# opencmpp.net
KiCad netlist of a schematic drawn in EAGLE
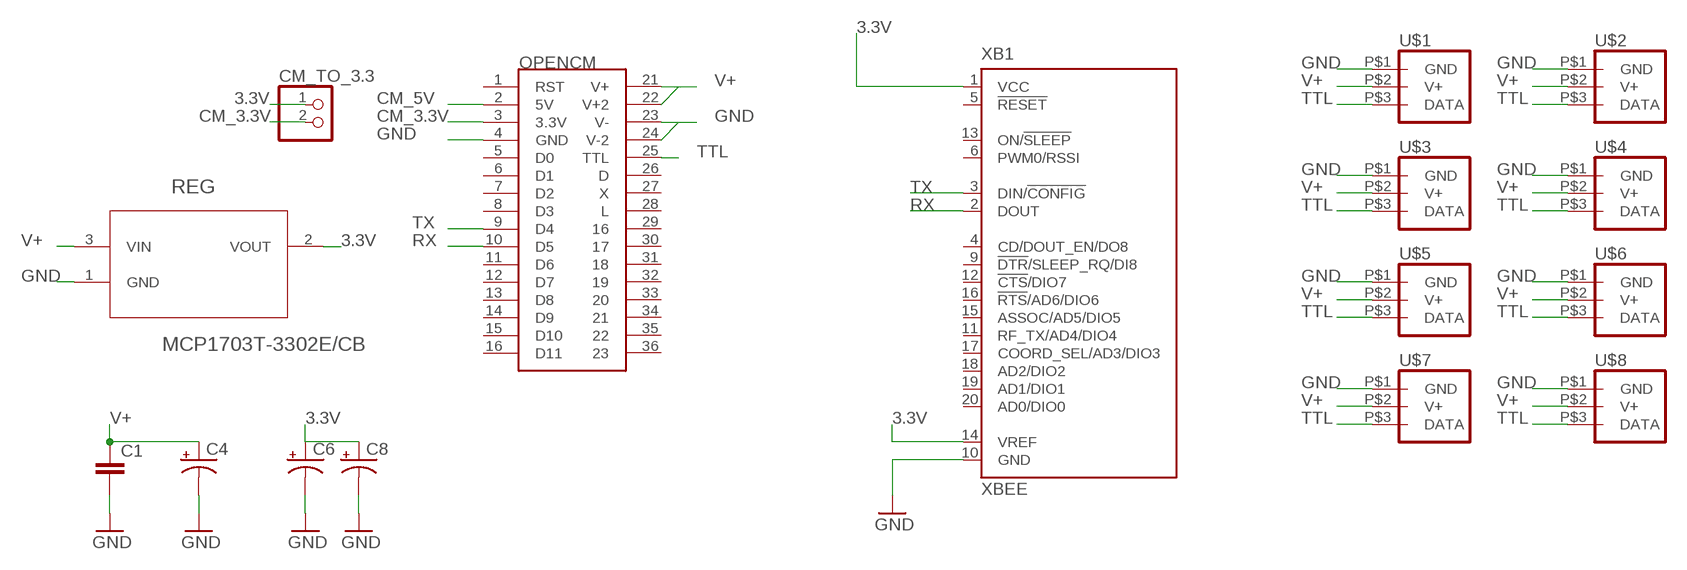
[diagram p0: schematic, sheet 1]

(export (version "E")
  (design (tool "Eeschema 10.0.6"))
  (components
    (comp (ref "C1")
      (value "C-EU075-032X103")
      (footprint "eagle-import:C075-032X103")
      (libsource (lib "eagle-import") (part "C-EU075-032X103"))
    )
    (comp (ref "C4")
      (value "CAP_POLPTH2")
      (footprint "eagle-import:CPOL-RADIAL-10UF-25V")
      (libsource (lib "eagle-import") (part "CAP_POLPTH2"))
    )
    (comp (ref "C6")
      (value "CAP_POLPTH2")
      (footprint "eagle-import:CPOL-RADIAL-10UF-25V")
      (libsource (lib "eagle-import") (part "CAP_POLPTH2"))
    )
    (comp (ref "C8")
      (value "CAP_POLPTH2")
      (footprint "eagle-import:CPOL-RADIAL-10UF-25V")
      (libsource (lib "eagle-import") (part "CAP_POLPTH2"))
    )
    (comp (ref "CM_TO_3.3")
      (value "CONNEC_1X02")
      (footprint "eagle-import:CONNEC_1X02")
      (libsource (lib "eagle-import") (part "CONNEC_1X02"))
    )
    (comp (ref "OPENCM")
      (value "OPENCM_REDUC")
      (footprint "eagle-import:OPENCM_REDUC")
      (libsource (lib "eagle-import") (part "OPENCM_REDUC"))
    )
    (comp (ref "REG")
      (value "MCP1703T-3302E/CB")
      (footprint "eagle-import:SOT95P300X145-3N")
      (libsource (lib "eagle-import") (part "MCP1703T-3302E/CB"))
    )
    (comp (ref "U$1")
      (value "XL_320_CONNEC")
      (footprint "eagle-import:DXL_320_CONNEC")
      (libsource (lib "eagle-import") (part "XL_320_CONNEC"))
    )
    (comp (ref "U$2")
      (value "XL_320_CONNEC")
      (footprint "eagle-import:DXL_320_CONNEC")
      (libsource (lib "eagle-import") (part "XL_320_CONNEC"))
    )
    (comp (ref "U$3")
      (value "XL_320_CONNEC")
      (footprint "eagle-import:DXL_320_CONNEC")
      (libsource (lib "eagle-import") (part "XL_320_CONNEC"))
    )
    (comp (ref "U$4")
      (value "XL_320_CONNEC")
      (footprint "eagle-import:DXL_320_CONNEC")
      (libsource (lib "eagle-import") (part "XL_320_CONNEC"))
    )
    (comp (ref "U$5")
      (value "XL_320_CONNEC")
      (footprint "eagle-import:DXL_320_CONNEC")
      (libsource (lib "eagle-import") (part "XL_320_CONNEC"))
    )
    (comp (ref "U$6")
      (value "XL_320_CONNEC")
      (footprint "eagle-import:DXL_320_CONNEC")
      (libsource (lib "eagle-import") (part "XL_320_CONNEC"))
    )
    (comp (ref "U$7")
      (value "XL_320_CONNEC")
      (footprint "eagle-import:DXL_320_CONNEC")
      (libsource (lib "eagle-import") (part "XL_320_CONNEC"))
    )
    (comp (ref "U$8")
      (value "XL_320_CONNEC")
      (footprint "eagle-import:DXL_320_CONNEC")
      (libsource (lib "eagle-import") (part "XL_320_CONNEC"))
    )
    (comp (ref "XB1")
      (value "XBEE")
      (footprint "eagle-import:XBEE")
      (fields (field (name "MPN") "XBP24-Z7UIT-004"))
      (libsource (lib "eagle-import") (part "XBEE"))
    )
  )
  (nets
    (net (code "1") (name "/3.3V") (class "Default")
      (node (ref "C6") (pin "1") (pinfunction "+_1") (pintype "passive"))
      (node (ref "C8") (pin "1") (pinfunction "+_1") (pintype "passive"))
      (node (ref "CM_TO_3.3") (pin "1") (pinfunction "1_1") (pintype "passive"))
      (node (ref "REG") (pin "2") (pinfunction "VOUT_2") (pintype "output"))
      (node (ref "XB1") (pin "1") (pinfunction "VCC_1") (pintype "power_in"))
      (node (ref "XB1") (pin "14") (pinfunction "VREF_14") (pintype "input"))
    )
    (net (code "2") (name "/CM_3.3V") (class "Default")
      (node (ref "CM_TO_3.3") (pin "2") (pinfunction "2_2") (pintype "passive"))
      (node (ref "OPENCM") (pin "3") (pinfunction "3.3V_3") (pintype "bidirectional"))
    )
    (net (code "3") (name "/CM_5V") (class "Default")
      (node (ref "OPENCM") (pin "2") (pinfunction "5V_2") (pintype "bidirectional"))
    )
    (net (code "4") (name "/RX") (class "Default")
      (node (ref "OPENCM") (pin "10") (pinfunction "D5_10") (pintype "bidirectional"))
      (node (ref "XB1") (pin "2") (pinfunction "DOUT_2") (pintype "output"))
    )
    (net (code "5") (name "/TTL") (class "Default")
      (node (ref "OPENCM") (pin "25") (pinfunction "TTL_25") (pintype "bidirectional"))
      (node (ref "U$1") (pin "P$3") (pinfunction "DATA_P$3") (pintype "bidirectional"))
      (node (ref "U$2") (pin "P$3") (pinfunction "DATA_P$3") (pintype "bidirectional"))
      (node (ref "U$3") (pin "P$3") (pinfunction "DATA_P$3") (pintype "bidirectional"))
      (node (ref "U$4") (pin "P$3") (pinfunction "DATA_P$3") (pintype "bidirectional"))
      (node (ref "U$5") (pin "P$3") (pinfunction "DATA_P$3") (pintype "bidirectional"))
      (node (ref "U$6") (pin "P$3") (pinfunction "DATA_P$3") (pintype "bidirectional"))
      (node (ref "U$7") (pin "P$3") (pinfunction "DATA_P$3") (pintype "bidirectional"))
      (node (ref "U$8") (pin "P$3") (pinfunction "DATA_P$3") (pintype "bidirectional"))
    )
    (net (code "6") (name "/TX") (class "Default")
      (node (ref "OPENCM") (pin "9") (pinfunction "D4_9") (pintype "bidirectional"))
      (node (ref "XB1") (pin "3") (pinfunction "DIN/~{CONFIG}_3") (pintype "input"))
    )
    (net (code "7") (name "/V+") (class "Default")
      (node (ref "C1") (pin "1") (pinfunction "1_1") (pintype "passive"))
      (node (ref "C4") (pin "1") (pinfunction "+_1") (pintype "passive"))
      (node (ref "OPENCM") (pin "21") (pinfunction "V+_21") (pintype "bidirectional"))
      (node (ref "OPENCM") (pin "22") (pinfunction "V+2_22") (pintype "bidirectional"))
      (node (ref "REG") (pin "3") (pinfunction "VIN_3") (pintype "input"))
      (node (ref "U$1") (pin "P$2") (pinfunction "V+_P$2") (pintype "bidirectional"))
      (node (ref "U$2") (pin "P$2") (pinfunction "V+_P$2") (pintype "bidirectional"))
      (node (ref "U$3") (pin "P$2") (pinfunction "V+_P$2") (pintype "bidirectional"))
      (node (ref "U$4") (pin "P$2") (pinfunction "V+_P$2") (pintype "bidirectional"))
      (node (ref "U$5") (pin "P$2") (pinfunction "V+_P$2") (pintype "bidirectional"))
      (node (ref "U$6") (pin "P$2") (pinfunction "V+_P$2") (pintype "bidirectional"))
      (node (ref "U$7") (pin "P$2") (pinfunction "V+_P$2") (pintype "bidirectional"))
      (node (ref "U$8") (pin "P$2") (pinfunction "V+_P$2") (pintype "bidirectional"))
    )
    (net (code "8") (name "GND") (class "Default")
      (node (ref "C1") (pin "2") (pinfunction "2_2") (pintype "passive"))
      (node (ref "C4") (pin "2") (pinfunction "-_2") (pintype "passive"))
      (node (ref "C6") (pin "2") (pinfunction "-_2") (pintype "passive"))
      (node (ref "C8") (pin "2") (pinfunction "-_2") (pintype "passive"))
      (node (ref "OPENCM") (pin "23") (pinfunction "V-_23") (pintype "bidirectional"))
      (node (ref "OPENCM") (pin "24") (pinfunction "V-2_24") (pintype "bidirectional"))
      (node (ref "OPENCM") (pin "4") (pinfunction "GND_4") (pintype "bidirectional"))
      (node (ref "REG") (pin "1") (pinfunction "GND_1") (pintype "passive"))
      (node (ref "U$1") (pin "P$1") (pinfunction "GND_P$1") (pintype "bidirectional"))
      (node (ref "U$2") (pin "P$1") (pinfunction "GND_P$1") (pintype "bidirectional"))
      (node (ref "U$3") (pin "P$1") (pinfunction "GND_P$1") (pintype "bidirectional"))
      (node (ref "U$4") (pin "P$1") (pinfunction "GND_P$1") (pintype "bidirectional"))
      (node (ref "U$5") (pin "P$1") (pinfunction "GND_P$1") (pintype "bidirectional"))
      (node (ref "U$6") (pin "P$1") (pinfunction "GND_P$1") (pintype "bidirectional"))
      (node (ref "U$7") (pin "P$1") (pinfunction "GND_P$1") (pintype "bidirectional"))
      (node (ref "U$8") (pin "P$1") (pinfunction "GND_P$1") (pintype "bidirectional"))
      (node (ref "XB1") (pin "10") (pinfunction "GND_10") (pintype "power_in"))
    )
    (net (code "9") (name "unconnected-(OPENCM-16-Pad29)") (class "Default")
      (node (ref "OPENCM") (pin "29") (pinfunction "16_29") (pintype "bidirectional"))
    )
    (net (code "10") (name "unconnected-(OPENCM-17-Pad30)") (class "Default")
      (node (ref "OPENCM") (pin "30") (pinfunction "17_30") (pintype "bidirectional"))
    )
    (net (code "11") (name "unconnected-(OPENCM-18-Pad31)") (class "Default")
      (node (ref "OPENCM") (pin "31") (pinfunction "18_31") (pintype "bidirectional"))
    )
    (net (code "12") (name "unconnected-(OPENCM-19-Pad32)") (class "Default")
      (node (ref "OPENCM") (pin "32") (pinfunction "19_32") (pintype "bidirectional"))
    )
    (net (code "13") (name "unconnected-(OPENCM-20-Pad33)") (class "Default")
      (node (ref "OPENCM") (pin "33") (pinfunction "20_33") (pintype "bidirectional"))
    )
    (net (code "14") (name "unconnected-(OPENCM-21-Pad34)") (class "Default")
      (node (ref "OPENCM") (pin "34") (pinfunction "21_34") (pintype "bidirectional"))
    )
    (net (code "15") (name "unconnected-(OPENCM-22-Pad35)") (class "Default")
      (node (ref "OPENCM") (pin "35") (pinfunction "22_35") (pintype "bidirectional"))
    )
    (net (code "16") (name "unconnected-(OPENCM-23-Pad36)") (class "Default")
      (node (ref "OPENCM") (pin "36") (pinfunction "23_36") (pintype "bidirectional"))
    )
    (net (code "17") (name "unconnected-(OPENCM-D-Pad26)") (class "Default")
      (node (ref "OPENCM") (pin "26") (pinfunction "D_26") (pintype "bidirectional"))
    )
    (net (code "18") (name "unconnected-(OPENCM-D0-Pad5)") (class "Default")
      (node (ref "OPENCM") (pin "5") (pinfunction "D0_5") (pintype "bidirectional"))
    )
    (net (code "19") (name "unconnected-(OPENCM-D1-Pad6)") (class "Default")
      (node (ref "OPENCM") (pin "6") (pinfunction "D1_6") (pintype "bidirectional"))
    )
    (net (code "20") (name "unconnected-(OPENCM-D2-Pad7)") (class "Default")
      (node (ref "OPENCM") (pin "7") (pinfunction "D2_7") (pintype "bidirectional"))
    )
    (net (code "21") (name "unconnected-(OPENCM-D3-Pad8)") (class "Default")
      (node (ref "OPENCM") (pin "8") (pinfunction "D3_8") (pintype "bidirectional"))
    )
    (net (code "22") (name "unconnected-(OPENCM-D6-Pad11)") (class "Default")
      (node (ref "OPENCM") (pin "11") (pinfunction "D6_11") (pintype "bidirectional"))
    )
    (net (code "23") (name "unconnected-(OPENCM-D7-Pad12)") (class "Default")
      (node (ref "OPENCM") (pin "12") (pinfunction "D7_12") (pintype "bidirectional"))
    )
    (net (code "24") (name "unconnected-(OPENCM-D8-Pad13)") (class "Default")
      (node (ref "OPENCM") (pin "13") (pinfunction "D8_13") (pintype "bidirectional"))
    )
    (net (code "25") (name "unconnected-(OPENCM-D9-Pad14)") (class "Default")
      (node (ref "OPENCM") (pin "14") (pinfunction "D9_14") (pintype "bidirectional"))
    )
    (net (code "26") (name "unconnected-(OPENCM-D10-Pad15)") (class "Default")
      (node (ref "OPENCM") (pin "15") (pinfunction "D10_15") (pintype "bidirectional"))
    )
    (net (code "27") (name "unconnected-(OPENCM-D11-Pad16)") (class "Default")
      (node (ref "OPENCM") (pin "16") (pinfunction "D11_16") (pintype "bidirectional"))
    )
    (net (code "28") (name "unconnected-(OPENCM-L-Pad28)") (class "Default")
      (node (ref "OPENCM") (pin "28") (pinfunction "L_28") (pintype "bidirectional"))
    )
    (net (code "29") (name "unconnected-(OPENCM-RST-Pad1)") (class "Default")
      (node (ref "OPENCM") (pin "1") (pinfunction "RST_1") (pintype "bidirectional"))
    )
    (net (code "30") (name "unconnected-(OPENCM-X-Pad27)") (class "Default")
      (node (ref "OPENCM") (pin "27") (pinfunction "X_27") (pintype "bidirectional"))
    )
    (net (code "31") (name "unconnected-(XB1-AD0{slash}DIO0-Pad20)") (class "Default")
      (node (ref "XB1") (pin "20") (pinfunction "AD0/DIO0_20") (pintype "bidirectional"))
    )
    (net (code "32") (name "unconnected-(XB1-AD1{slash}DIO1-Pad19)") (class "Default")
      (node (ref "XB1") (pin "19") (pinfunction "AD1/DIO1_19") (pintype "bidirectional"))
    )
    (net (code "33") (name "unconnected-(XB1-AD2{slash}DIO2-Pad18)") (class "Default")
      (node (ref "XB1") (pin "18") (pinfunction "AD2/DIO2_18") (pintype "bidirectional"))
    )
    (net (code "34") (name "unconnected-(XB1-ASSOC{slash}AD5{slash}DIO5-Pad15)") (class "Default")
      (node (ref "XB1") (pin "15") (pinfunction "ASSOC/AD5/DIO5_15") (pintype "bidirectional"))
    )
    (net (code "35") (name "unconnected-(XB1-CD{slash}DOUT_EN{slash}DO8-Pad4)") (class "Default")
      (node (ref "XB1") (pin "4") (pinfunction "CD/DOUT_EN/DO8_4") (pintype "output"))
    )
    (net (code "36") (name "unconnected-(XB1-COORD_SEL{slash}AD3{slash}DIO3-Pad17)") (class "Default")
      (node (ref "XB1") (pin "17") (pinfunction "COORD_SEL/AD3/DIO3_17") (pintype "bidirectional"))
    )
    (net (code "37") (name "unconnected-(XB1-ON{slash}~{SLEEP}-Pad13)") (class "Default")
      (node (ref "XB1") (pin "13") (pinfunction "ON/~{SLEEP}_13") (pintype "output"))
    )
    (net (code "38") (name "unconnected-(XB1-PWM0{slash}RSSI-Pad6)") (class "Default")
      (node (ref "XB1") (pin "6") (pinfunction "PWM0/RSSI_6") (pintype "output"))
    )
    (net (code "39") (name "unconnected-(XB1-RF_TX{slash}AD4{slash}DIO4-Pad11)") (class "Default")
      (node (ref "XB1") (pin "11") (pinfunction "RF_TX/AD4/DIO4_11") (pintype "bidirectional"))
    )
    (net (code "40") (name "unconnected-(XB1-~{CTS}{slash}DIO7-Pad12)") (class "Default")
      (node (ref "XB1") (pin "12") (pinfunction "~{CTS}/DIO7_12") (pintype "bidirectional"))
    )
    (net (code "41") (name "unconnected-(XB1-~{DTR}{slash}SLEEP_RQ{slash}DI8-Pad9)") (class "Default")
      (node (ref "XB1") (pin "9") (pinfunction "~{DTR}/SLEEP_RQ/DI8_9") (pintype "bidirectional"))
    )
    (net (code "42") (name "unconnected-(XB1-~{RESET}-Pad5)") (class "Default")
      (node (ref "XB1") (pin "5") (pinfunction "~{RESET}_5") (pintype "input"))
    )
    (net (code "43") (name "unconnected-(XB1-~{RTS}{slash}AD6{slash}DIO6-Pad16)") (class "Default")
      (node (ref "XB1") (pin "16") (pinfunction "~{RTS}/AD6/DIO6_16") (pintype "bidirectional"))
    )
  )
)
